# master.net
KiCad netlist of a schematic drawn in EAGLE
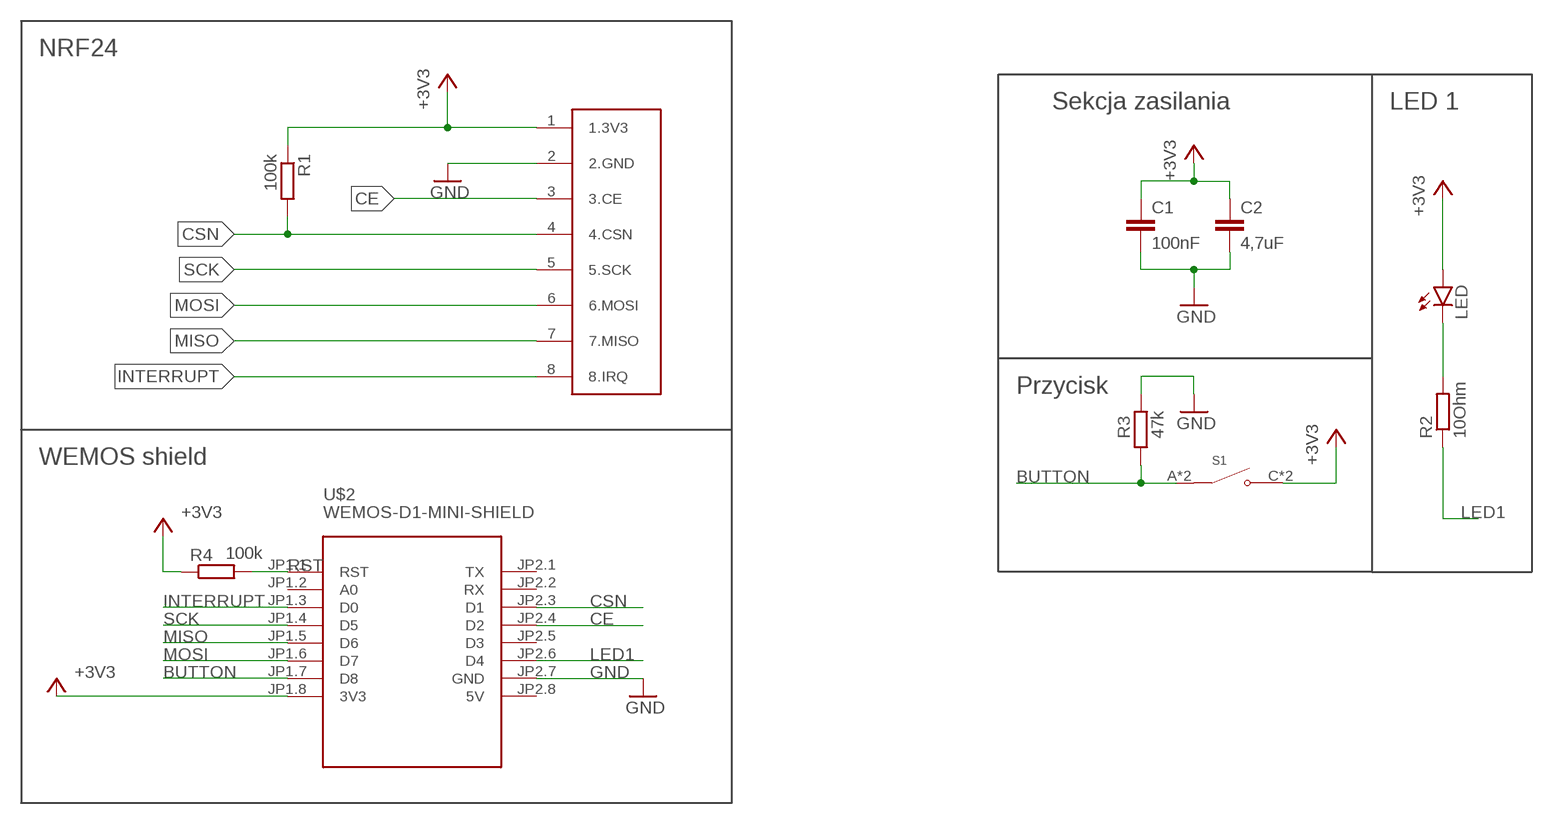
[diagram p0: schematic, sheet 1]

(export (version "E")
  (design (tool "Eeschema 10.0.6"))
  (components
    (comp (ref "C1")
      (value "100nF")
      (footprint "eagle-import:C0805")
      (libsource (lib "eagle-import") (part "C-EUC0805"))
    )
    (comp (ref "C2")
      (value "4,7uF")
      (footprint "eagle-import:C025-050X050")
      (libsource (lib "eagle-import") (part "C-EU025-050X050"))
    )
    (comp (ref "LED")
      (value "LEDCHIP-LED0805")
      (footprint "eagle-import:CHIP-LED0805")
      (libsource (lib "eagle-import") (part "LEDCHIP-LED0805"))
    )
    (comp (ref "NRF24")
      (value "NRF24L01+")
      (footprint "eagle-import:NRF24L01+")
      (libsource (lib "eagle-import") (part "NRF24L01+"))
    )
    (comp (ref "R1")
      (value "100k")
      (footprint "eagle-import:M0805")
      (libsource (lib "eagle-import") (part "R-EU_M0805"))
    )
    (comp (ref "R2")
      (value "10Ohm")
      (footprint "eagle-import:M0805")
      (libsource (lib "eagle-import") (part "R-EU_M0805"))
    )
    (comp (ref "R3")
      (value "47k")
      (footprint "eagle-import:M0805")
      (libsource (lib "eagle-import") (part "R-EU_M0805"))
    )
    (comp (ref "R4")
      (value "100k")
      (footprint "eagle-import:M0805")
      (libsource (lib "eagle-import") (part "R-EU_M0805"))
    )
    (comp (ref "S1")
      (value "TS-1187A-B-A-B")
      (footprint "eagle-import:SW_TS-1187A-B-A-B")
      (libsource (lib "eagle-import") (part "TS-1187A-B-A-B"))
    )
    (comp (ref "U$2")
      (value "WEMOS-D1-MINI-SHIELD")
      (footprint "eagle-import:WEMOS-D1-MINI-SHIELD")
      (libsource (lib "eagle-import") (part "WEMOS-D1-MINI-SHIELD"))
    )
  )
  (nets
    (net (code "1") (name "+3V3") (class "Default")
      (node (ref "C1") (pin "1") (pinfunction "1_1") (pintype "passive"))
      (node (ref "C2") (pin "1") (pinfunction "1_1") (pintype "passive"))
      (node (ref "LED") (pin "A") (pinfunction "A_A") (pintype "passive"))
      (node (ref "NRF24") (pin "1") (pinfunction "1.3V3_1") (pintype "bidirectional"))
      (node (ref "R1") (pin "1") (pinfunction "1_1") (pintype "passive"))
      (node (ref "R4") (pin "1") (pinfunction "1_1") (pintype "passive"))
      (node (ref "S1") (pin "C") (pinfunction "NO_C") (pintype "passive"))
      (node (ref "S1") (pin "D") (pinfunction "NO_D") (pintype "passive"))
      (node (ref "U$2") (pin "JP1.8") (pinfunction "3V3_JP1.8") (pintype "power_in"))
    )
    (net (code "2") (name "/5V") (class "Default")
      (node (ref "U$2") (pin "JP2.8") (pinfunction "5V_JP2.8") (pintype "power_in"))
    )
    (net (code "3") (name "/BUTTON") (class "Default")
      (node (ref "R3") (pin "1") (pinfunction "1_1") (pintype "passive"))
      (node (ref "S1") (pin "A") (pinfunction "COM_A") (pintype "passive"))
      (node (ref "S1") (pin "B") (pinfunction "COM_B") (pintype "passive"))
      (node (ref "U$2") (pin "JP1.7") (pinfunction "D8_JP1.7") (pintype "bidirectional"))
    )
    (net (code "4") (name "/LED1") (class "Default")
      (node (ref "R2") (pin "1") (pinfunction "1_1") (pintype "passive"))
      (node (ref "U$2") (pin "JP2.6") (pinfunction "D4_JP2.6") (pintype "bidirectional"))
    )
    (net (code "5") (name "/RST") (class "Default")
      (node (ref "R4") (pin "2") (pinfunction "2_2") (pintype "passive"))
      (node (ref "U$2") (pin "JP1.1") (pinfunction "RST_JP1.1") (pintype "bidirectional"))
    )
    (net (code "6") (name "CE") (class "Default")
      (node (ref "NRF24") (pin "3") (pinfunction "3.CE_3") (pintype "bidirectional"))
      (node (ref "U$2") (pin "JP2.4") (pinfunction "D2_JP2.4") (pintype "bidirectional"))
    )
    (net (code "7") (name "CSN") (class "Default")
      (node (ref "NRF24") (pin "4") (pinfunction "4.CSN_4") (pintype "bidirectional"))
      (node (ref "R1") (pin "2") (pinfunction "2_2") (pintype "passive"))
      (node (ref "U$2") (pin "JP2.3") (pinfunction "D1_JP2.3") (pintype "bidirectional"))
    )
    (net (code "8") (name "GND") (class "Default")
      (node (ref "C1") (pin "2") (pinfunction "2_2") (pintype "passive"))
      (node (ref "C2") (pin "2") (pinfunction "2_2") (pintype "passive"))
      (node (ref "NRF24") (pin "2") (pinfunction "2.GND_2") (pintype "bidirectional"))
      (node (ref "R3") (pin "2") (pinfunction "2_2") (pintype "passive"))
      (node (ref "U$2") (pin "JP2.7") (pinfunction "GND_JP2.7") (pintype "power_in"))
    )
    (net (code "9") (name "INTERRUPT") (class "Default")
      (node (ref "NRF24") (pin "8") (pinfunction "8.IRQ_8") (pintype "bidirectional"))
      (node (ref "U$2") (pin "JP1.3") (pinfunction "D0_JP1.3") (pintype "bidirectional"))
    )
    (net (code "10") (name "MISO") (class "Default")
      (node (ref "NRF24") (pin "7") (pinfunction "7.MISO_7") (pintype "bidirectional"))
      (node (ref "U$2") (pin "JP1.5") (pinfunction "D6_JP1.5") (pintype "bidirectional"))
    )
    (net (code "11") (name "MOSI") (class "Default")
      (node (ref "NRF24") (pin "6") (pinfunction "6.MOSI_6") (pintype "bidirectional"))
      (node (ref "U$2") (pin "JP1.6") (pinfunction "D7_JP1.6") (pintype "bidirectional"))
    )
    (net (code "12") (name "Net-(LED-PadC)") (class "Default")
      (node (ref "LED") (pin "C") (pinfunction "C_C") (pintype "passive"))
      (node (ref "R2") (pin "2") (pinfunction "2_2") (pintype "passive"))
    )
    (net (code "13") (name "SCK") (class "Default")
      (node (ref "NRF24") (pin "5") (pinfunction "5.SCK_5") (pintype "bidirectional"))
      (node (ref "U$2") (pin "JP1.4") (pinfunction "D5_JP1.4") (pintype "bidirectional"))
    )
    (net (code "14") (name "unconnected-(U$2-A0-PadJP1.2)") (class "Default")
      (node (ref "U$2") (pin "JP1.2") (pinfunction "A0_JP1.2") (pintype "bidirectional"))
    )
    (net (code "15") (name "unconnected-(U$2-D3-PadJP2.5)") (class "Default")
      (node (ref "U$2") (pin "JP2.5") (pinfunction "D3_JP2.5") (pintype "bidirectional"))
    )
    (net (code "16") (name "unconnected-(U$2-RX-PadJP2.2)") (class "Default")
      (node (ref "U$2") (pin "JP2.2") (pinfunction "RX_JP2.2") (pintype "bidirectional"))
    )
    (net (code "17") (name "unconnected-(U$2-TX-PadJP2.1)") (class "Default")
      (node (ref "U$2") (pin "JP2.1") (pinfunction "TX_JP2.1") (pintype "bidirectional"))
    )
  )
)
